# Slave.net
KiCad netlist of a schematic drawn in Altium Designer
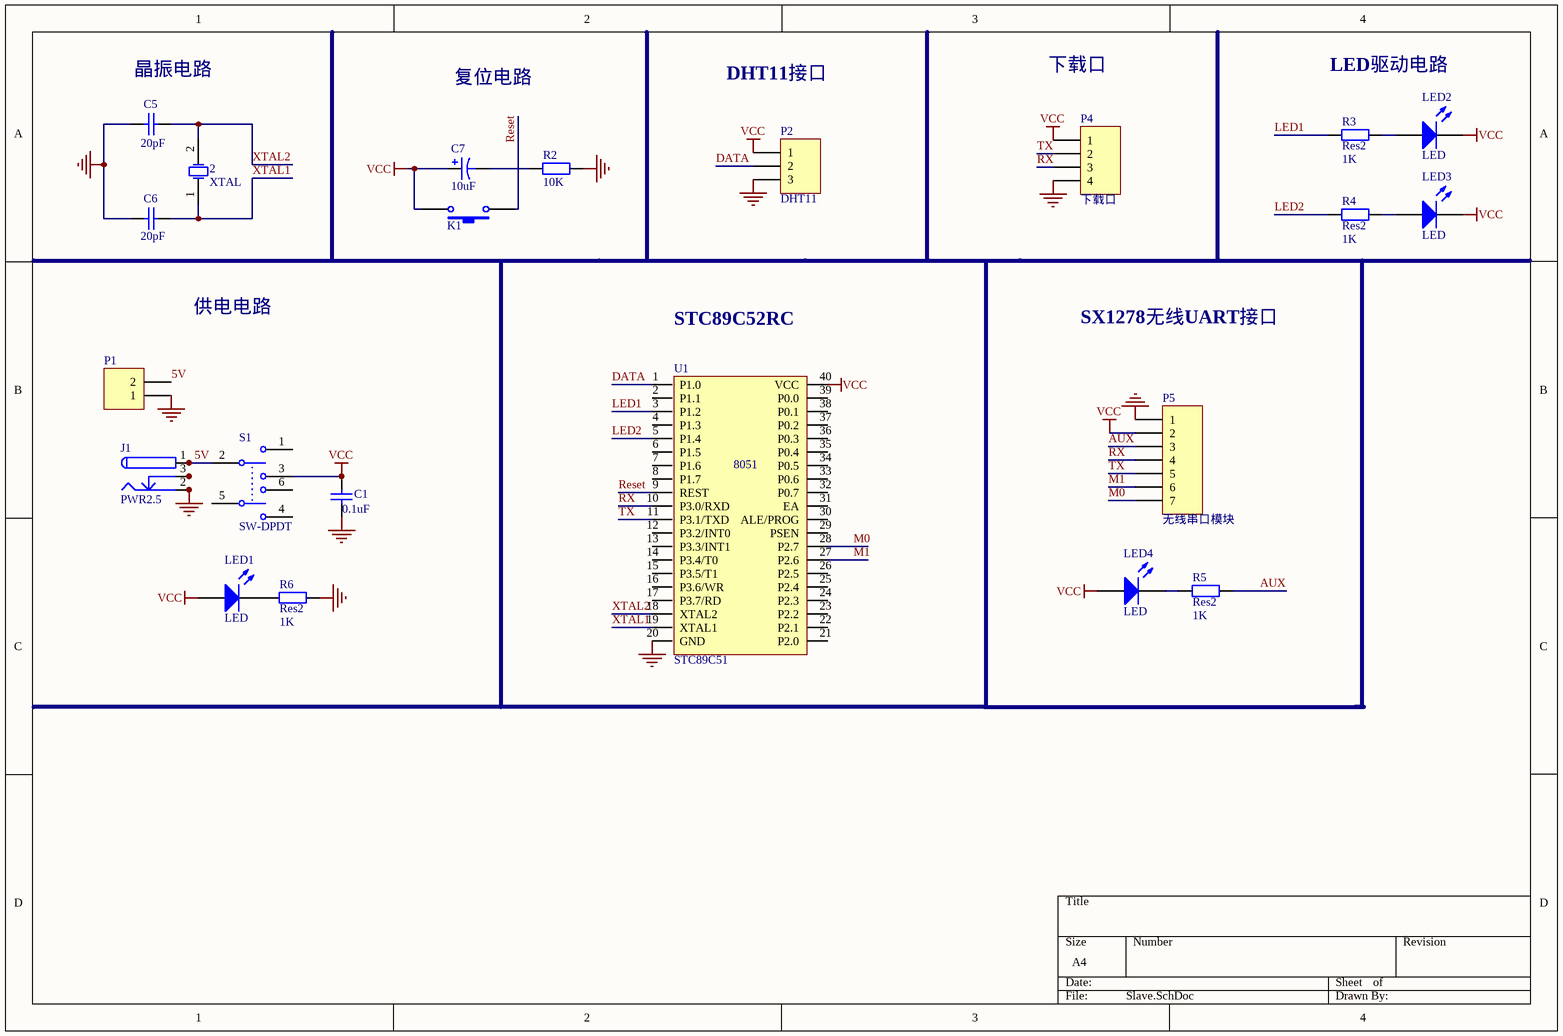
[diagram p0: Slave.SchDoc]

(export (version "E")
  (design (tool "Eeschema 10.0.6"))
  (components
    (comp (ref "2")
      (value "XTAL")
      (footprint "XTAL_US")
      (description "Crystal Oscillator")
      (fields (field (name "PUBLISHER") "Altium Limited"))
      (libsource (lib "Miscellaneous Devices") (part "XTAL"))
    )
    (comp (ref "C1")
      (value "0.1uF")
      (footprint "RAD-0.1")
      (description "Capacitor")
      (fields (field (name "Comment") "Cap") (field (name "PUBLISHER") "Altium Limited"))
      (libsource (lib "Miscellaneous Devices") (part "Cap"))
    )
    (comp (ref "C5")
      (value "20pF")
      (footprint "RAD-0.1")
      (description "Capacitor")
      (fields (field (name "Comment") "Cap") (field (name "PUBLISHER") "Altium Limited"))
      (libsource (lib "Miscellaneous Devices") (part "Cap"))
    )
    (comp (ref "C6")
      (value "20pF")
      (footprint "RAD-0.1")
      (description "Capacitor")
      (fields (field (name "Comment") "Cap") (field (name "PUBLISHER") "Altium Limited"))
      (libsource (lib "Miscellaneous Devices") (part "Cap"))
    )
    (comp (ref "C7")
      (value "10uF")
      (footprint "RB.1/.2")
      (description "Polarized Capacitor (Radial)")
      (fields (field (name "Comment") "Cap Pol1") (field (name "PUBLISHER") "Altium Limited"))
      (libsource (lib "Miscellaneous Devices") (part "Cap Pol1"))
    )
    (comp (ref "J1")
      (value "PWR2.5")
      (footprint "KLD-0202")
      (description "Low Voltage Power Supply Connector")
      (fields (field (name "PUBLISHER") "Altium Limited"))
      (libsource (lib "Miscellaneous Connectors") (part "PWR2.5"))
    )
    (comp (ref "K1") (value "四脚按键") (footprint "四脚按键") (libsource (lib "My library") (part "四脚按键")))
    (comp (ref "LED1") (value "LED") (footprint "LED") (libsource (lib "My library") (part "LED")))
    (comp (ref "LED2") (value "LED") (footprint "LED") (libsource (lib "My library") (part "LED")))
    (comp (ref "LED3") (value "LED") (footprint "LED") (libsource (lib "My library") (part "LED")))
    (comp (ref "LED4") (value "LED") (footprint "LED") (libsource (lib "My library") (part "LED")))
    (comp (ref "P1")
      (value "~")
      (footprint "HDR1X2")
      (description "Header, 2-Pin")
      (fields (field (name "PUBLISHER") "Altium Limited"))
      (libsource (lib "Miscellaneous Connectors") (part "Header 2"))
    )
    (comp (ref "P2")
      (value "DHT11")
      (footprint "HDR1X3")
      (description "Header, 3-Pin")
      (fields (field (name "PUBLISHER") "Altium Limited"))
      (libsource (lib "Miscellaneous Connectors") (part "Header 3"))
    )
    (comp (ref "P4")
      (value "下载口")
      (footprint "HDR1X4")
      (description "Header, 4-Pin")
      (fields (field (name "PUBLISHER") "Altium Limited"))
      (libsource (lib "Miscellaneous Connectors") (part "Header 4"))
    )
    (comp (ref "P5")
      (value "无线串口模块")
      (footprint "AS32-TTL-100")
      (description "Header, 7-Pin")
      (fields (field (name "PUBLISHER") "Altium Limited"))
      (libsource (lib "Miscellaneous Connectors") (part "Header 7"))
    )
    (comp (ref "R2")
      (value "10K")
      (footprint "AXIAL-0.4")
      (description "Resistor")
      (fields (field (name "Comment") "Res2") (field (name "PUBLISHER") "Altium Limited"))
      (libsource (lib "Miscellaneous Devices") (part "Res2"))
    )
    (comp (ref "R3")
      (value "Res2")
      (footprint "AXIAL-0.4")
      (description "Resistor")
      (fields (field (name "ALTIUM_VALUE") "1K") (field (name "PUBLISHER") "Altium Limited"))
      (libsource (lib "Miscellaneous Devices") (part "Res2"))
    )
    (comp (ref "R4")
      (value "Res2")
      (footprint "AXIAL-0.4")
      (description "Resistor")
      (fields (field (name "ALTIUM_VALUE") "1K") (field (name "PUBLISHER") "Altium Limited"))
      (libsource (lib "Miscellaneous Devices") (part "Res2"))
    )
    (comp (ref "R5")
      (value "Res2")
      (footprint "AXIAL-0.4")
      (description "Resistor")
      (fields (field (name "ALTIUM_VALUE") "1K") (field (name "PUBLISHER") "Altium Limited"))
      (libsource (lib "Miscellaneous Devices") (part "Res2"))
    )
    (comp (ref "R6")
      (value "Res2")
      (footprint "AXIAL-0.4")
      (description "Resistor")
      (fields (field (name "ALTIUM_VALUE") "1K") (field (name "PUBLISHER") "Altium Limited"))
      (libsource (lib "Miscellaneous Devices") (part "Res2"))
    )
    (comp (ref "S1")
      (value "SW-DPDT")
      (footprint "SWITCH_B1")
      (description "单刀双掷开关")
      (fields (field (name "PUBLISHER") "Altium Limited"))
      (libsource (lib "Fszhang") (part "SW-DPDT"))
    )
    (comp (ref "U1") (value "STC89C51") (footprint "DIP-40") (libsource (lib "My library") (part "STC89C51")))
  )
  (nets
    (net (code "1") (name "/5V") (class "Default")
      (node (ref "J1") (pin "1") (pinfunction "1_1") (pintype "power_in"))
      (node (ref "J1") (pin "1A") (pinfunction "1A_1A") (pintype "power_in"))
      (node (ref "J1") (pin "1B") (pinfunction "1B_1B") (pintype "power_in"))
      (node (ref "P1") (pin "2") (pinfunction "2_2") (pintype "passive"))
      (node (ref "S1") (pin "2") (pinfunction "2_2") (pintype "passive"))
    )
    (net (code "2") (name "/AUX") (class "Default")
      (node (ref "P5") (pin "3") (pinfunction "3_3") (pintype "passive"))
      (node (ref "R5") (pin "2") (pinfunction "2_2") (pintype "passive"))
    )
    (net (code "3") (name "/DATA") (class "Default")
      (node (ref "P2") (pin "2") (pinfunction "2_2") (pintype "passive"))
      (node (ref "U1") (pin "1") (pinfunction "P1.0_1") (pintype "passive"))
    )
    (net (code "4") (name "/LED1") (class "Default")
      (node (ref "R3") (pin "1") (pinfunction "1_1") (pintype "passive"))
      (node (ref "U1") (pin "3") (pinfunction "P1.2_3") (pintype "passive"))
    )
    (net (code "5") (name "/LED2") (class "Default")
      (node (ref "R4") (pin "1") (pinfunction "1_1") (pintype "passive"))
      (node (ref "U1") (pin "5") (pinfunction "P1.4_5") (pintype "passive"))
    )
    (net (code "6") (name "/M0") (class "Default")
      (node (ref "P5") (pin "7") (pinfunction "7_7") (pintype "passive"))
      (node (ref "U1") (pin "28") (pinfunction "P2.7_28") (pintype "passive"))
    )
    (net (code "7") (name "/M1") (class "Default")
      (node (ref "P5") (pin "6") (pinfunction "6_6") (pintype "passive"))
      (node (ref "U1") (pin "27") (pinfunction "P2.6_27") (pintype "passive"))
    )
    (net (code "8") (name "/RX") (class "Default")
      (node (ref "P4") (pin "3") (pinfunction "3_3") (pintype "passive"))
      (node (ref "P5") (pin "4") (pinfunction "4_4") (pintype "passive"))
      (node (ref "U1") (pin "10") (pinfunction "P3.0/RXD_10") (pintype "passive"))
    )
    (net (code "9") (name "/Reset") (class "Default")
      (node (ref "K1") (pin "1") (pinfunction "1_1") (pintype "passive"))
      (node (ref "U1") (pin "9") (pinfunction "REST_9") (pintype "passive"))
    )
    (net (code "10") (name "/TX") (class "Default")
      (node (ref "P4") (pin "2") (pinfunction "2_2") (pintype "passive"))
      (node (ref "P5") (pin "5") (pinfunction "5_5") (pintype "passive"))
      (node (ref "U1") (pin "11") (pinfunction "P3.1/TXD_11") (pintype "passive"))
    )
    (net (code "11") (name "/XTAL1") (class "Default")
      (node (ref "2") (pin "1") (pinfunction "OSC1_1") (pintype "passive"))
      (node (ref "C6") (pin "2") (pinfunction "2_2") (pintype "passive"))
      (node (ref "U1") (pin "19") (pinfunction "XTAL1_19") (pintype "passive"))
    )
    (net (code "12") (name "/XTAL2") (class "Default")
      (node (ref "2") (pin "2") (pinfunction "OSC2_2") (pintype "passive"))
      (node (ref "C5") (pin "2") (pinfunction "2_2") (pintype "passive"))
      (node (ref "U1") (pin "18") (pinfunction "XTAL2_18") (pintype "passive"))
    )
    (net (code "13") (name "GND") (class "Default")
      (node (ref "C1") (pin "1") (pinfunction "1_1") (pintype "passive"))
      (node (ref "C5") (pin "1") (pinfunction "1_1") (pintype "passive"))
      (node (ref "C6") (pin "1") (pinfunction "1_1") (pintype "passive"))
      (node (ref "J1") (pin "2") (pinfunction "2_2") (pintype "power_in"))
      (node (ref "J1") (pin "2A") (pinfunction "2A_2A") (pintype "power_in"))
      (node (ref "J1") (pin "2B") (pinfunction "2B_2B") (pintype "power_in"))
      (node (ref "P1") (pin "1") (pinfunction "1_1") (pintype "passive"))
      (node (ref "P2") (pin "3") (pinfunction "3_3") (pintype "passive"))
      (node (ref "P4") (pin "4") (pinfunction "4_4") (pintype "passive"))
      (node (ref "P5") (pin "1") (pinfunction "1_1") (pintype "passive"))
      (node (ref "R2") (pin "2") (pinfunction "2_2") (pintype "passive"))
      (node (ref "R6") (pin "2") (pinfunction "2_2") (pintype "passive"))
      (node (ref "U1") (pin "20") (pinfunction "GND_20") (pintype "passive"))
    )
    (net (code "14") (name "Net-(C7-Pad2)") (class "Default")
      (node (ref "C7") (pin "2") (pinfunction "2_2") (pintype "passive"))
      (node (ref "R2") (pin "1") (pinfunction "1_1") (pintype "passive"))
    )
    (net (code "15") (name "Net-(J1-Pad3)") (class "Default")
      (node (ref "J1") (pin "3") (pinfunction "3_3") (pintype "power_in"))
      (node (ref "J1") (pin "3A") (pinfunction "3A_3A") (pintype "power_in"))
      (node (ref "J1") (pin "3B") (pinfunction "3B_3B") (pintype "power_in"))
    )
    (net (code "16") (name "Net-(LED1-Pad2)") (class "Default")
      (node (ref "LED1") (pin "2") (pinfunction "2_2") (pintype "passive"))
      (node (ref "R6") (pin "1") (pinfunction "1_1") (pintype "passive"))
    )
    (net (code "17") (name "Net-(LED2-Pad1)") (class "Default")
      (node (ref "LED2") (pin "1") (pinfunction "1_1") (pintype "passive"))
      (node (ref "R3") (pin "2") (pinfunction "2_2") (pintype "passive"))
    )
    (net (code "18") (name "Net-(LED3-Pad1)") (class "Default")
      (node (ref "LED3") (pin "1") (pinfunction "1_1") (pintype "passive"))
      (node (ref "R4") (pin "2") (pinfunction "2_2") (pintype "passive"))
    )
    (net (code "19") (name "Net-(LED4-Pad2)") (class "Default")
      (node (ref "LED4") (pin "2") (pinfunction "2_2") (pintype "passive"))
      (node (ref "R5") (pin "1") (pinfunction "1_1") (pintype "passive"))
    )
    (net (code "20") (name "VCC") (class "Default")
      (node (ref "C1") (pin "2") (pinfunction "2_2") (pintype "passive"))
      (node (ref "C7") (pin "1") (pinfunction "1_1") (pintype "passive"))
      (node (ref "K1") (pin "2") (pinfunction "2_2") (pintype "passive"))
      (node (ref "LED1") (pin "1") (pinfunction "1_1") (pintype "passive"))
      (node (ref "LED2") (pin "2") (pinfunction "2_2") (pintype "passive"))
      (node (ref "LED3") (pin "2") (pinfunction "2_2") (pintype "passive"))
      (node (ref "LED4") (pin "1") (pinfunction "1_1") (pintype "passive"))
      (node (ref "P2") (pin "1") (pinfunction "1_1") (pintype "passive"))
      (node (ref "P4") (pin "1") (pinfunction "1_1") (pintype "passive"))
      (node (ref "P5") (pin "2") (pinfunction "2_2") (pintype "passive"))
      (node (ref "S1") (pin "3") (pinfunction "3_3") (pintype "passive"))
      (node (ref "U1") (pin "40") (pinfunction "VCC_40") (pintype "passive"))
    )
    (net (code "21") (name "unconnected-(S1-Pad1)") (class "Default")
      (node (ref "S1") (pin "1") (pinfunction "1_1") (pintype "passive"))
    )
    (net (code "22") (name "unconnected-(S1-Pad4)") (class "Default")
      (node (ref "S1") (pin "4") (pinfunction "4_4") (pintype "passive"))
    )
    (net (code "23") (name "unconnected-(S1-Pad5)") (class "Default")
      (node (ref "S1") (pin "5") (pinfunction "5_5") (pintype "passive"))
    )
    (net (code "24") (name "unconnected-(S1-Pad6)") (class "Default")
      (node (ref "S1") (pin "6") (pinfunction "6_6") (pintype "passive"))
    )
    (net (code "25") (name "unconnected-(U1-ALE{slash}PROG-Pad30)") (class "Default")
      (node (ref "U1") (pin "30") (pinfunction "ALE/PROG_30") (pintype "passive"))
    )
    (net (code "26") (name "unconnected-(U1-EA-Pad31)") (class "Default")
      (node (ref "U1") (pin "31") (pinfunction "EA_31") (pintype "passive"))
    )
    (net (code "27") (name "unconnected-(U1-P0.0-Pad39)") (class "Default")
      (node (ref "U1") (pin "39") (pinfunction "P0.0_39") (pintype "passive"))
    )
    (net (code "28") (name "unconnected-(U1-P0.1-Pad38)") (class "Default")
      (node (ref "U1") (pin "38") (pinfunction "P0.1_38") (pintype "passive"))
    )
    (net (code "29") (name "unconnected-(U1-P0.2-Pad37)") (class "Default")
      (node (ref "U1") (pin "37") (pinfunction "P0.2_37") (pintype "passive"))
    )
    (net (code "30") (name "unconnected-(U1-P0.3-Pad36)") (class "Default")
      (node (ref "U1") (pin "36") (pinfunction "P0.3_36") (pintype "passive"))
    )
    (net (code "31") (name "unconnected-(U1-P0.4-Pad35)") (class "Default")
      (node (ref "U1") (pin "35") (pinfunction "P0.4_35") (pintype "passive"))
    )
    (net (code "32") (name "unconnected-(U1-P0.5-Pad34)") (class "Default")
      (node (ref "U1") (pin "34") (pinfunction "P0.5_34") (pintype "passive"))
    )
    (net (code "33") (name "unconnected-(U1-P0.6-Pad33)") (class "Default")
      (node (ref "U1") (pin "33") (pinfunction "P0.6_33") (pintype "passive"))
    )
    (net (code "34") (name "unconnected-(U1-P0.7-Pad32)") (class "Default")
      (node (ref "U1") (pin "32") (pinfunction "P0.7_32") (pintype "passive"))
    )
    (net (code "35") (name "unconnected-(U1-P1.1-Pad2)") (class "Default")
      (node (ref "U1") (pin "2") (pinfunction "P1.1_2") (pintype "passive"))
    )
    (net (code "36") (name "unconnected-(U1-P1.3-Pad4)") (class "Default")
      (node (ref "U1") (pin "4") (pinfunction "P1.3_4") (pintype "passive"))
    )
    (net (code "37") (name "unconnected-(U1-P1.5-Pad6)") (class "Default")
      (node (ref "U1") (pin "6") (pinfunction "P1.5_6") (pintype "passive"))
    )
    (net (code "38") (name "unconnected-(U1-P1.6-Pad7)") (class "Default")
      (node (ref "U1") (pin "7") (pinfunction "P1.6_7") (pintype "passive"))
    )
    (net (code "39") (name "unconnected-(U1-P1.7-Pad8)") (class "Default")
      (node (ref "U1") (pin "8") (pinfunction "P1.7_8") (pintype "passive"))
    )
    (net (code "40") (name "unconnected-(U1-P2.0-Pad21)") (class "Default")
      (node (ref "U1") (pin "21") (pinfunction "P2.0_21") (pintype "passive"))
    )
    (net (code "41") (name "unconnected-(U1-P2.1-Pad22)") (class "Default")
      (node (ref "U1") (pin "22") (pinfunction "P2.1_22") (pintype "passive"))
    )
    (net (code "42") (name "unconnected-(U1-P2.2-Pad23)") (class "Default")
      (node (ref "U1") (pin "23") (pinfunction "P2.2_23") (pintype "passive"))
    )
    (net (code "43") (name "unconnected-(U1-P2.3-Pad24)") (class "Default")
      (node (ref "U1") (pin "24") (pinfunction "P2.3_24") (pintype "passive"))
    )
    (net (code "44") (name "unconnected-(U1-P2.4-Pad25)") (class "Default")
      (node (ref "U1") (pin "25") (pinfunction "P2.4_25") (pintype "passive"))
    )
    (net (code "45") (name "unconnected-(U1-P2.5-Pad26)") (class "Default")
      (node (ref "U1") (pin "26") (pinfunction "P2.5_26") (pintype "passive"))
    )
    (net (code "46") (name "unconnected-(U1-P3.2{slash}INT0-Pad12)") (class "Default")
      (node (ref "U1") (pin "12") (pinfunction "P3.2/INT0_12") (pintype "passive"))
    )
    (net (code "47") (name "unconnected-(U1-P3.3{slash}INT1-Pad13)") (class "Default")
      (node (ref "U1") (pin "13") (pinfunction "P3.3/INT1_13") (pintype "passive"))
    )
    (net (code "48") (name "unconnected-(U1-P3.4{slash}T0-Pad14)") (class "Default")
      (node (ref "U1") (pin "14") (pinfunction "P3.4/T0_14") (pintype "passive"))
    )
    (net (code "49") (name "unconnected-(U1-P3.5{slash}T1-Pad15)") (class "Default")
      (node (ref "U1") (pin "15") (pinfunction "P3.5/T1_15") (pintype "passive"))
    )
    (net (code "50") (name "unconnected-(U1-P3.6{slash}WR-Pad16)") (class "Default")
      (node (ref "U1") (pin "16") (pinfunction "P3.6/WR_16") (pintype "passive"))
    )
    (net (code "51") (name "unconnected-(U1-P3.7{slash}RD-Pad17)") (class "Default")
      (node (ref "U1") (pin "17") (pinfunction "P3.7/RD_17") (pintype "passive"))
    )
    (net (code "52") (name "unconnected-(U1-PSEN-Pad29)") (class "Default")
      (node (ref "U1") (pin "29") (pinfunction "PSEN_29") (pintype "passive"))
    )
  )
)
